# expansion.net
KiCad netlist of a schematic drawn in Altium Designer
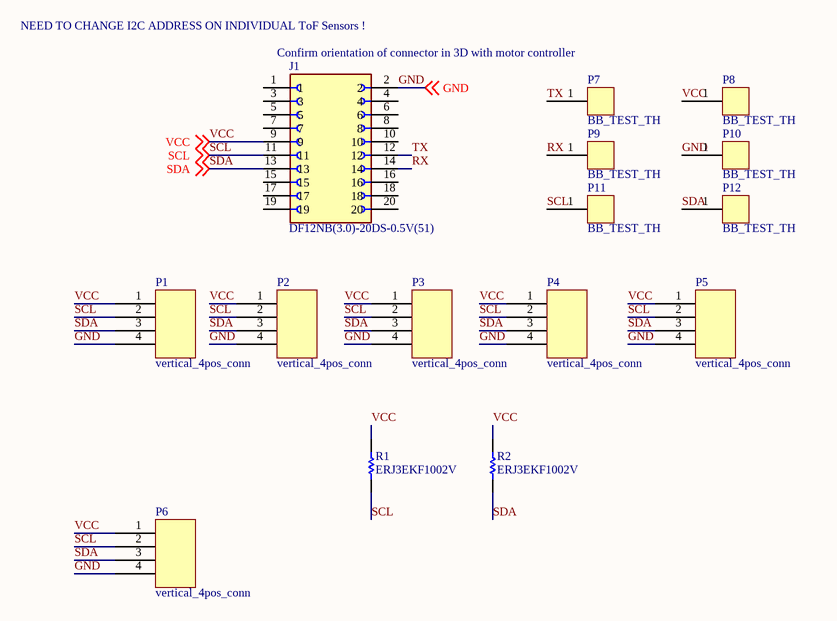
[diagram p0: expansion.SchDoc]

(export (version "E")
  (design (tool "Eeschema 10.0.6"))
  (components
    (comp (ref "J1")
      (value "DF12NB(3.0)-20DS-0.5V(51)")
      (footprint "HRS_DF12NB(3.0)-20DS-0.5V(51)")
      (libsource (lib "expansion_library") (part "DF12NB(3.0)-20DS-0.5V(51)"))
    )
    (comp (ref "P1")
      (value "vertical_4pos_conn")
      (footprint "vertical_4pos_conn _s_square")
      (libsource (lib "expansion_library") (part "vertical_4pos_conn"))
    )
    (comp (ref "P2")
      (value "vertical_4pos_conn")
      (footprint "vertical_4pos_conn _s_square")
      (libsource (lib "expansion_library") (part "vertical_4pos_conn"))
    )
    (comp (ref "P3")
      (value "vertical_4pos_conn")
      (footprint "vertical_4pos_conn _s_square")
      (libsource (lib "expansion_library") (part "vertical_4pos_conn"))
    )
    (comp (ref "P4")
      (value "vertical_4pos_conn")
      (footprint "vertical_4pos_conn _s_square")
      (libsource (lib "expansion_library") (part "vertical_4pos_conn"))
    )
    (comp (ref "P5")
      (value "vertical_4pos_conn")
      (footprint "vertical_4pos_conn _s_square")
      (libsource (lib "expansion_library") (part "vertical_4pos_conn"))
    )
    (comp (ref "P6")
      (value "vertical_4pos_conn")
      (footprint "4pos_conn_tof")
      (libsource (lib "expansion_library") (part "vertical_4pos_conn"))
    )
    (comp (ref "P7")
      (value "BB_TEST_TH")
      (footprint "BB_WIRE_TEST_TH")
      (libsource (lib "expansion_library") (part "BB_TEST_TH"))
    )
    (comp (ref "P8")
      (value "BB_TEST_TH")
      (footprint "BB_WIRE_TEST_TH")
      (libsource (lib "expansion_library") (part "BB_TEST_TH"))
    )
    (comp (ref "P9")
      (value "BB_TEST_TH")
      (footprint "BB_WIRE_TEST_TH")
      (libsource (lib "expansion_library") (part "BB_TEST_TH"))
    )
    (comp (ref "P10")
      (value "BB_TEST_TH")
      (footprint "BB_WIRE_TEST_TH")
      (libsource (lib "expansion_library") (part "BB_TEST_TH"))
    )
    (comp (ref "P11")
      (value "BB_TEST_TH")
      (footprint "BB_WIRE_TEST_TH")
      (libsource (lib "expansion_library") (part "BB_TEST_TH"))
    )
    (comp (ref "P12")
      (value "BB_TEST_TH")
      (footprint "BB_WIRE_TEST_TH")
      (libsource (lib "expansion_library") (part "BB_TEST_TH"))
    )
    (comp (ref "R1")
      (value "ERJ3EKF1002V")
      (footprint "RESC1609X55X30LL15T15")
      (description "Chip Resistor, 10 KOhm, +/- 1%, 0.1 W, -55 to 155 degC, 0603 (1608 Metric), RoHS, Tape and Reel")
      (fields (field (name "TOLERANCE") "1%") (field (name "MANUFACTURER") "Panasonic"))
      (libsource (lib "Altium Content Vault") (part "RES-2"))
    )
    (comp (ref "R2")
      (value "ERJ3EKF1002V")
      (footprint "RESC1609X55X30LL15T15")
      (description "Chip Resistor, 10 KOhm, +/- 1%, 0.1 W, -55 to 155 degC, 0603 (1608 Metric), RoHS, Tape and Reel")
      (fields (field (name "TOLERANCE") "1%") (field (name "MANUFACTURER") "Panasonic"))
      (libsource (lib "Altium Content Vault") (part "RES-2"))
    )
  )
  (nets
    (net (code "1") (name "/RX") (class "Default")
      (node (ref "J1") (pin "14") (pinfunction "14_14") (pintype "passive"))
      (node (ref "P9") (pin "1") (pinfunction "1_1") (pintype "passive"))
    )
    (net (code "2") (name "/TX") (class "Default")
      (node (ref "J1") (pin "12") (pinfunction "12_12") (pintype "passive"))
      (node (ref "P7") (pin "1") (pinfunction "1_1") (pintype "passive"))
    )
    (net (code "3") (name "GND") (class "Default")
      (node (ref "J1") (pin "2") (pinfunction "2_2") (pintype "passive"))
      (node (ref "P1") (pin "4") (pinfunction "4_4") (pintype "passive"))
      (node (ref "P10") (pin "1") (pinfunction "1_1") (pintype "passive"))
      (node (ref "P2") (pin "4") (pinfunction "4_4") (pintype "passive"))
      (node (ref "P3") (pin "4") (pinfunction "4_4") (pintype "passive"))
      (node (ref "P4") (pin "4") (pinfunction "4_4") (pintype "passive"))
      (node (ref "P5") (pin "4") (pinfunction "4_4") (pintype "passive"))
      (node (ref "P6") (pin "4") (pinfunction "4_4") (pintype "passive"))
    )
    (net (code "4") (name "SCL") (class "Default")
      (node (ref "J1") (pin "11") (pinfunction "11_11") (pintype "passive"))
      (node (ref "P1") (pin "2") (pinfunction "2_2") (pintype "passive"))
      (node (ref "P11") (pin "1") (pinfunction "1_1") (pintype "passive"))
      (node (ref "P2") (pin "2") (pinfunction "2_2") (pintype "passive"))
      (node (ref "P3") (pin "2") (pinfunction "2_2") (pintype "passive"))
      (node (ref "P4") (pin "2") (pinfunction "2_2") (pintype "passive"))
      (node (ref "P5") (pin "2") (pinfunction "2_2") (pintype "passive"))
      (node (ref "P6") (pin "2") (pinfunction "2_2") (pintype "passive"))
      (node (ref "R1") (pin "1") (pinfunction "1_1") (pintype "passive"))
    )
    (net (code "5") (name "SDA") (class "Default")
      (node (ref "J1") (pin "13") (pinfunction "13_13") (pintype "passive"))
      (node (ref "P1") (pin "3") (pinfunction "3_3") (pintype "passive"))
      (node (ref "P12") (pin "1") (pinfunction "1_1") (pintype "passive"))
      (node (ref "P2") (pin "3") (pinfunction "3_3") (pintype "passive"))
      (node (ref "P3") (pin "3") (pinfunction "3_3") (pintype "passive"))
      (node (ref "P4") (pin "3") (pinfunction "3_3") (pintype "passive"))
      (node (ref "P5") (pin "3") (pinfunction "3_3") (pintype "passive"))
      (node (ref "P6") (pin "3") (pinfunction "3_3") (pintype "passive"))
      (node (ref "R2") (pin "1") (pinfunction "1_1") (pintype "passive"))
    )
    (net (code "6") (name "VCC") (class "Default")
      (node (ref "J1") (pin "9") (pinfunction "9_9") (pintype "passive"))
      (node (ref "P1") (pin "1") (pinfunction "1_1") (pintype "passive"))
      (node (ref "P2") (pin "1") (pinfunction "1_1") (pintype "passive"))
      (node (ref "P3") (pin "1") (pinfunction "1_1") (pintype "passive"))
      (node (ref "P4") (pin "1") (pinfunction "1_1") (pintype "passive"))
      (node (ref "P5") (pin "1") (pinfunction "1_1") (pintype "passive"))
      (node (ref "P6") (pin "1") (pinfunction "1_1") (pintype "passive"))
      (node (ref "P8") (pin "1") (pinfunction "1_1") (pintype "passive"))
      (node (ref "R1") (pin "2") (pinfunction "2_2") (pintype "passive"))
      (node (ref "R2") (pin "2") (pinfunction "2_2") (pintype "passive"))
    )
    (net (code "7") (name "unconnected-(J1-Pad1)") (class "Default")
      (node (ref "J1") (pin "1") (pinfunction "1_1") (pintype "passive"))
    )
    (net (code "8") (name "unconnected-(J1-Pad3)") (class "Default")
      (node (ref "J1") (pin "3") (pinfunction "3_3") (pintype "passive"))
    )
    (net (code "9") (name "unconnected-(J1-Pad4)") (class "Default")
      (node (ref "J1") (pin "4") (pinfunction "4_4") (pintype "passive"))
    )
    (net (code "10") (name "unconnected-(J1-Pad5)") (class "Default")
      (node (ref "J1") (pin "5") (pinfunction "5_5") (pintype "passive"))
    )
    (net (code "11") (name "unconnected-(J1-Pad6)") (class "Default")
      (node (ref "J1") (pin "6") (pinfunction "6_6") (pintype "passive"))
    )
    (net (code "12") (name "unconnected-(J1-Pad7)") (class "Default")
      (node (ref "J1") (pin "7") (pinfunction "7_7") (pintype "passive"))
    )
    (net (code "13") (name "unconnected-(J1-Pad8)") (class "Default")
      (node (ref "J1") (pin "8") (pinfunction "8_8") (pintype "passive"))
    )
    (net (code "14") (name "unconnected-(J1-Pad10)") (class "Default")
      (node (ref "J1") (pin "10") (pinfunction "10_10") (pintype "passive"))
    )
    (net (code "15") (name "unconnected-(J1-Pad15)") (class "Default")
      (node (ref "J1") (pin "15") (pinfunction "15_15") (pintype "passive"))
    )
    (net (code "16") (name "unconnected-(J1-Pad16)") (class "Default")
      (node (ref "J1") (pin "16") (pinfunction "16_16") (pintype "passive"))
    )
    (net (code "17") (name "unconnected-(J1-Pad17)") (class "Default")
      (node (ref "J1") (pin "17") (pinfunction "17_17") (pintype "passive"))
    )
    (net (code "18") (name "unconnected-(J1-Pad18)") (class "Default")
      (node (ref "J1") (pin "18") (pinfunction "18_18") (pintype "passive"))
    )
    (net (code "19") (name "unconnected-(J1-Pad19)") (class "Default")
      (node (ref "J1") (pin "19") (pinfunction "19_19") (pintype "passive"))
    )
    (net (code "20") (name "unconnected-(J1-Pad20)") (class "Default")
      (node (ref "J1") (pin "20") (pinfunction "20_20") (pintype "passive"))
    )
  )
)
